# Finger_IMU_PCB.net
KiCad netlist of a schematic drawn in Altium Designer
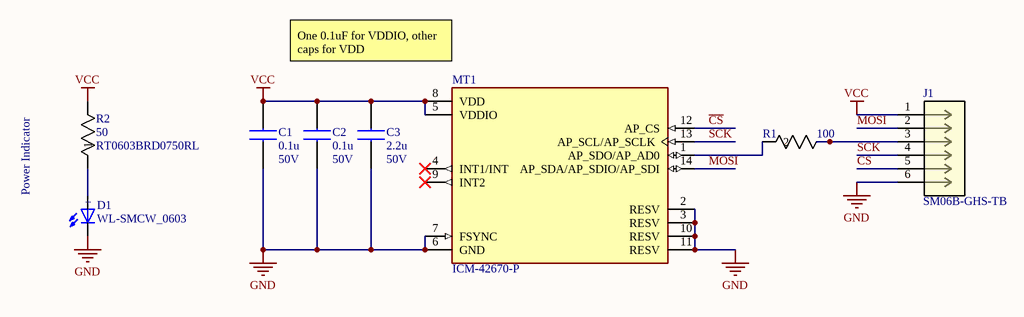
[diagram p0: Finger_IMU_PCB.SchDoc]

(export (version "E")
  (design (tool "Eeschema 10.0.6"))
  (components
    (comp (ref "C1")
      (value "0.1u")
      (footprint "CAPC2012X145N")
      (description "Multilayer Ceramic Chip Capacitors, Capacitance=0.1u")
      (fields
        (field (name "MANUFACTURER_PART_NUMBER") "KAM21BR71H104JM")
        (field (name "RATED VOLTAGE") "50V")
      )
      (libsource (lib "Caps") (part "KAM21BR71H104JM"))
    )
    (comp (ref "C2")
      (value "0.1u")
      (footprint "CAPC2012X145N")
      (description "Multilayer Ceramic Chip Capacitors, Capacitance=0.1u")
      (fields
        (field (name "MANUFACTURER_PART_NUMBER") "KAM21BR71H104JM")
        (field (name "RATED VOLTAGE") "50V")
      )
      (libsource (lib "Caps") (part "KAM21BR71H104JM"))
    )
    (comp (ref "C3")
      (value "2.2u")
      (footprint "CAPC2012X145N")
      (description "Multilayer Ceramic Chip Capacitors, Capacitance=2.2u")
      (fields
        (field (name "MANUFACTURER_PART_NUMBER") "C2012X7R1H225K125AE")
        (field (name "RATED VOLTAGE") "50V")
      )
      (libsource (lib "Caps") (part "C2012X7R1H225K125AE"))
    )
    (comp (ref "D1")
      (value "WL-SMCW_0603")
      (footprint "WL-SMCW_0603")
      (description "0603, Yellow Typ.(@20mA): 590nm, 120mcd, 2.0V, 140Â° AlInGaP")
      (fields (field (name "MF") "Wurth Electronics") (field (name "MP") "150060YS75000"))
      (libsource (lib "WL-SMCW_0603") (part "WL-SMCW_0603"))
    )
    (comp (ref "J1")
      (value "SM06B-GHS-TB")
      (footprint "CONN_SM06B-GHS-TB_JST")
      (description "No Description Available")
      (fields (field (name "COPYRIGHT") "Copyright (C) 2025 Ultra Librarian. All rights reserved."))
      (libsource (lib "SM06B-GHS-TB") (part "SM06B-GHS-TB"))
    )
    (comp (ref "MT1")
      (value "ICM-42670-P")
      (footprint "XDCR_ICM-42670-P")
      (libsource (lib "ICM-42670-P") (part "ICM-42670-P"))
    )
    (comp (ref "R1")
      (value "100")
      (footprint "RC0805N_YAG")
      (description "RES 0805 100 5% 1/8W")
      (fields (field (name "MANUFACTURER_PART_NUMBER") "RC0805JR-07100RL") (field (name "TOLERANCE") "5%"))
      (libsource (lib "Resistors") (part "RC0805JR-07100RL"))
    )
    (comp (ref "R2")
      (value "RT0603BRD0750RL")
      (footprint "RES_RT0603_YAG")
      (description "No Description Available")
      (fields
        (field (name "ALTIUM_VALUE") "50")
        (field (name "COPYRIGHT") "Copyright (C) 2025 Ultra Librarian. All rights reserved.")
      )
      (libsource (lib "RT0603BRD0750RL") (part "RT0603BRD0750RL"))
    )
  )
  (nets
    (net (code "1") (name "/MOSI") (class "Default")
      (node (ref "J1") (pin "2") (pinfunction "2_2") (pintype "passive"))
      (node (ref "MT1") (pin "14") (pinfunction "AP_SDA/AP_SDIO/AP_SDI_14") (pintype "bidirectional"))
    )
    (net (code "2") (name "/SCK") (class "Default")
      (node (ref "J1") (pin "4") (pinfunction "4_4") (pintype "passive"))
      (node (ref "MT1") (pin "13") (pinfunction "AP_SCL/AP_SCLK_13") (pintype "input"))
    )
    (net (code "3") (name "/~{CS}") (class "Default")
      (node (ref "J1") (pin "5") (pinfunction "5_5") (pintype "passive"))
      (node (ref "MT1") (pin "12") (pinfunction "AP_CS_12") (pintype "input"))
    )
    (net (code "4") (name "GND") (class "Default")
      (node (ref "C1") (pin "1") (pinfunction "1_1") (pintype "passive"))
      (node (ref "C2") (pin "1") (pinfunction "1_1") (pintype "passive"))
      (node (ref "C3") (pin "1") (pinfunction "1_1") (pintype "passive"))
      (node (ref "D1") (pin "1") (pinfunction "NEG_1") (pintype "passive"))
      (node (ref "J1") (pin "6") (pinfunction "6_6") (pintype "passive"))
      (node (ref "MT1") (pin "10") (pinfunction "RESV_10") (pintype "passive"))
      (node (ref "MT1") (pin "11") (pinfunction "RESV_11") (pintype "passive"))
      (node (ref "MT1") (pin "2") (pinfunction "RESV_2") (pintype "passive"))
      (node (ref "MT1") (pin "3") (pinfunction "RESV_3") (pintype "passive"))
      (node (ref "MT1") (pin "6") (pinfunction "GND_6") (pintype "power_in"))
      (node (ref "MT1") (pin "7") (pinfunction "FSYNC_7") (pintype "input"))
    )
    (net (code "5") (name "Net-(D1-POS)") (class "Default")
      (node (ref "D1") (pin "2") (pinfunction "POS_2") (pintype "passive"))
      (node (ref "R2") (pin "1") (pinfunction "1_1") (pintype "passive"))
    )
    (net (code "6") (name "Net-(J1-Pad3)") (class "Default")
      (node (ref "J1") (pin "3") (pinfunction "3_3") (pintype "passive"))
      (node (ref "R1") (pin "1") (pinfunction "1_1") (pintype "passive"))
    )
    (net (code "7") (name "Net-(MT1-AP_SDO{slash}AP_AD0)") (class "Default")
      (node (ref "MT1") (pin "1") (pinfunction "AP_SDO/AP_AD0_1") (pintype "bidirectional"))
      (node (ref "R1") (pin "2") (pinfunction "2_2") (pintype "passive"))
    )
    (net (code "8") (name "VCC") (class "Default")
      (node (ref "C1") (pin "2") (pinfunction "2_2") (pintype "passive"))
      (node (ref "C2") (pin "2") (pinfunction "2_2") (pintype "passive"))
      (node (ref "C3") (pin "2") (pinfunction "2_2") (pintype "passive"))
      (node (ref "J1") (pin "1") (pinfunction "1_1") (pintype "passive"))
      (node (ref "MT1") (pin "5") (pinfunction "VDDIO_5") (pintype "power_in"))
      (node (ref "MT1") (pin "8") (pinfunction "VDD_8") (pintype "power_in"))
      (node (ref "R2") (pin "2") (pinfunction "2_2") (pintype "passive"))
    )
    (net (code "9") (name "unconnected-(MT1-INT1{slash}INT-Pad4)") (class "Default")
      (node (ref "MT1") (pin "4") (pinfunction "INT1/INT_4") (pintype "output+no_connect"))
    )
    (net (code "10") (name "unconnected-(MT1-INT2-Pad9)") (class "Default")
      (node (ref "MT1") (pin "9") (pinfunction "INT2_9") (pintype "output+no_connect"))
    )
  )
)
